# Connectors.net
KiCad netlist of a schematic drawn in Altium Designer
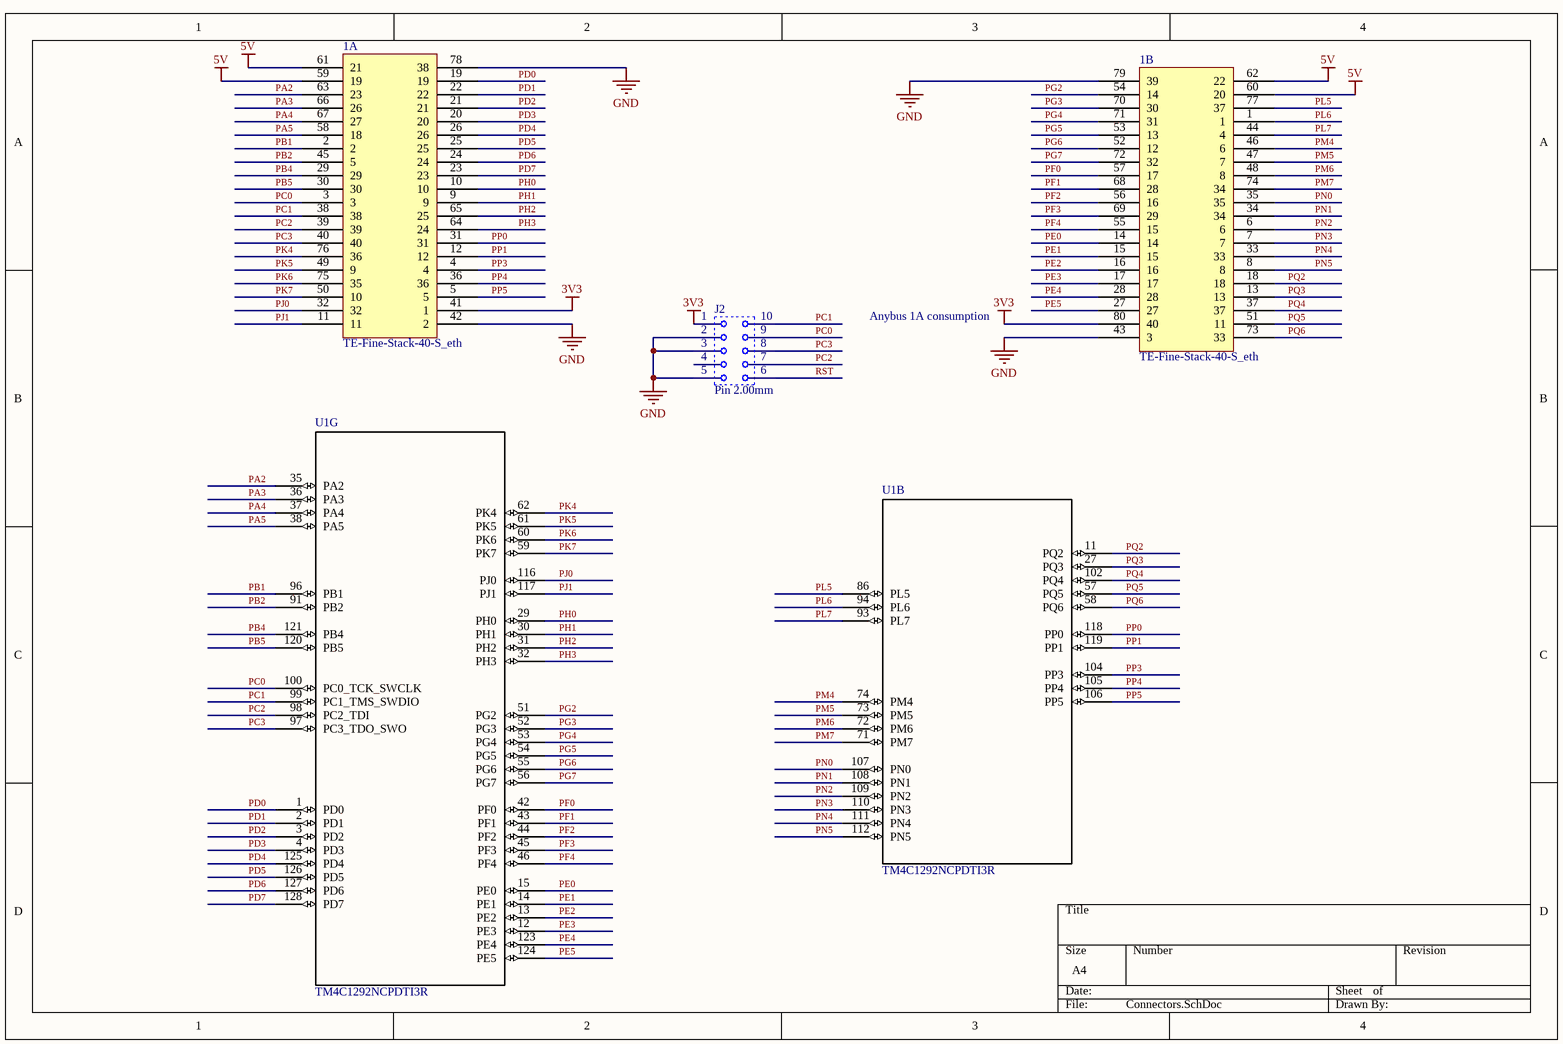
[diagram p0: Connectors.SchDoc]

(export (version "E")
  (design (tool "Eeschema 10.0.6"))
  (components
    (comp (ref "1")
      (value "TE-Fine-Stack-40-S_eth")
      (footprint "TE-FINE-STACK-40-S-Eth")
      (libsource (lib "Connectors") (part "TE-Fine-Stack-40-S_eth"))
    )
    (comp (ref "J2")
      (value "Pin 2.00mm")
      (footprint "GOLDPIN 1.27MM SOCKET 2X5 SMD")
      (libsource (lib "Connectors") (part "Goldpin 1.27 socket 2x5"))
    )
    (comp (ref "U1")
      (value "TM4C1292NCPDTI3R")
      (footprint "PDT0128A_N")
      (description "Imported")
      (fields
        (field (name "ALTERNATE PARTNUMBER") "TM4C1292NCPDTI3")
        (field (name "MANUFACTURER") "Texas Instruments")
      )
      (libsource (lib "TM4C129ENCPDT") (part "TM4C1292NCPDTI3R"))
    )
  )
  (nets
    (net (code "1") (name "/PA2") (class "Default")
      (node (ref "1") (pin "63") (pinfunction "23_63") (pintype "passive"))
      (node (ref "U1") (pin "35") (pinfunction "PA2_35") (pintype "bidirectional"))
    )
    (net (code "2") (name "/PA3") (class "Default")
      (node (ref "1") (pin "66") (pinfunction "26_66") (pintype "passive"))
      (node (ref "U1") (pin "36") (pinfunction "PA3_36") (pintype "bidirectional"))
    )
    (net (code "3") (name "/PA4") (class "Default")
      (node (ref "1") (pin "67") (pinfunction "27_67") (pintype "passive"))
      (node (ref "U1") (pin "37") (pinfunction "PA4_37") (pintype "bidirectional"))
    )
    (net (code "4") (name "/PA5") (class "Default")
      (node (ref "1") (pin "58") (pinfunction "18_58") (pintype "passive"))
      (node (ref "U1") (pin "38") (pinfunction "PA5_38") (pintype "bidirectional"))
    )
    (net (code "5") (name "/PB1") (class "Default")
      (node (ref "1") (pin "2") (pinfunction "2_2") (pintype "passive"))
      (node (ref "U1") (pin "96") (pinfunction "PB1_96") (pintype "bidirectional"))
    )
    (net (code "6") (name "/PB2") (class "Default")
      (node (ref "1") (pin "45") (pinfunction "5_45") (pintype "passive"))
      (node (ref "U1") (pin "91") (pinfunction "PB2_91") (pintype "bidirectional"))
    )
    (net (code "7") (name "/PB4") (class "Default")
      (node (ref "1") (pin "29") (pinfunction "29_29") (pintype "passive"))
      (node (ref "U1") (pin "121") (pinfunction "PB4_121") (pintype "bidirectional"))
    )
    (net (code "8") (name "/PB5") (class "Default")
      (node (ref "1") (pin "30") (pinfunction "30_30") (pintype "passive"))
      (node (ref "U1") (pin "120") (pinfunction "PB5_120") (pintype "bidirectional"))
    )
    (net (code "9") (name "/PC0") (class "Default")
      (node (ref "1") (pin "3") (pinfunction "3_3") (pintype "passive"))
      (node (ref "J2") (pin "9") (pintype "passive"))
      (node (ref "U1") (pin "100") (pinfunction "PC0_TCK_SWCLK_100") (pintype "bidirectional"))
    )
    (net (code "10") (name "/PC1") (class "Default")
      (node (ref "1") (pin "38") (pinfunction "38_38") (pintype "passive"))
      (node (ref "J2") (pin "10") (pintype "passive"))
      (node (ref "U1") (pin "99") (pinfunction "PC1_TMS_SWDIO_99") (pintype "bidirectional"))
    )
    (net (code "11") (name "/PC2") (class "Default")
      (node (ref "1") (pin "39") (pinfunction "39_39") (pintype "passive"))
      (node (ref "J2") (pin "7") (pintype "passive"))
      (node (ref "U1") (pin "98") (pinfunction "PC2_TDI_98") (pintype "bidirectional"))
    )
    (net (code "12") (name "/PC3") (class "Default")
      (node (ref "1") (pin "40") (pinfunction "40_40") (pintype "passive"))
      (node (ref "J2") (pin "8") (pintype "passive"))
      (node (ref "U1") (pin "97") (pinfunction "PC3_TDO_SWO_97") (pintype "bidirectional"))
    )
    (net (code "13") (name "/PD0") (class "Default")
      (node (ref "1") (pin "19") (pinfunction "19_19") (pintype "passive"))
      (node (ref "U1") (pin "1") (pinfunction "PD0_1") (pintype "bidirectional"))
    )
    (net (code "14") (name "/PD1") (class "Default")
      (node (ref "1") (pin "22") (pinfunction "22_22") (pintype "passive"))
      (node (ref "U1") (pin "2") (pinfunction "PD1_2") (pintype "bidirectional"))
    )
    (net (code "15") (name "/PD2") (class "Default")
      (node (ref "1") (pin "21") (pinfunction "21_21") (pintype "passive"))
      (node (ref "U1") (pin "3") (pinfunction "PD2_3") (pintype "bidirectional"))
    )
    (net (code "16") (name "/PD3") (class "Default")
      (node (ref "1") (pin "20") (pinfunction "20_20") (pintype "passive"))
      (node (ref "U1") (pin "4") (pinfunction "PD3_4") (pintype "bidirectional"))
    )
    (net (code "17") (name "/PD4") (class "Default")
      (node (ref "1") (pin "26") (pinfunction "26_26") (pintype "passive"))
      (node (ref "U1") (pin "125") (pinfunction "PD4_125") (pintype "bidirectional"))
    )
    (net (code "18") (name "/PD5") (class "Default")
      (node (ref "1") (pin "25") (pinfunction "25_25") (pintype "passive"))
      (node (ref "U1") (pin "126") (pinfunction "PD5_126") (pintype "bidirectional"))
    )
    (net (code "19") (name "/PD6") (class "Default")
      (node (ref "1") (pin "24") (pinfunction "24_24") (pintype "passive"))
      (node (ref "U1") (pin "127") (pinfunction "PD6_127") (pintype "bidirectional"))
    )
    (net (code "20") (name "/PD7") (class "Default")
      (node (ref "1") (pin "23") (pinfunction "23_23") (pintype "passive"))
      (node (ref "U1") (pin "128") (pinfunction "PD7_128") (pintype "bidirectional"))
    )
    (net (code "21") (name "/PE0") (class "Default")
      (node (ref "1") (pin "14") (pinfunction "14_14") (pintype "passive"))
      (node (ref "U1") (pin "15") (pinfunction "PE0_15") (pintype "bidirectional"))
    )
    (net (code "22") (name "/PE1") (class "Default")
      (node (ref "1") (pin "15") (pinfunction "15_15") (pintype "passive"))
      (node (ref "U1") (pin "14") (pinfunction "PE1_14") (pintype "bidirectional"))
    )
    (net (code "23") (name "/PE2") (class "Default")
      (node (ref "1") (pin "16") (pinfunction "16_16") (pintype "passive"))
      (node (ref "U1") (pin "13") (pinfunction "PE2_13") (pintype "bidirectional"))
    )
    (net (code "24") (name "/PE3") (class "Default")
      (node (ref "1") (pin "17") (pinfunction "17_17") (pintype "passive"))
      (node (ref "U1") (pin "12") (pinfunction "PE3_12") (pintype "bidirectional"))
    )
    (net (code "25") (name "/PE4") (class "Default")
      (node (ref "1") (pin "28") (pinfunction "28_28") (pintype "passive"))
      (node (ref "U1") (pin "123") (pinfunction "PE4_123") (pintype "bidirectional"))
    )
    (net (code "26") (name "/PE5") (class "Default")
      (node (ref "1") (pin "27") (pinfunction "27_27") (pintype "passive"))
      (node (ref "U1") (pin "124") (pinfunction "PE5_124") (pintype "bidirectional"))
    )
    (net (code "27") (name "/PF0") (class "Default")
      (node (ref "1") (pin "57") (pinfunction "17_57") (pintype "passive"))
      (node (ref "U1") (pin "42") (pinfunction "PF0_42") (pintype "bidirectional"))
    )
    (net (code "28") (name "/PF1") (class "Default")
      (node (ref "1") (pin "68") (pinfunction "28_68") (pintype "passive"))
      (node (ref "U1") (pin "43") (pinfunction "PF1_43") (pintype "bidirectional"))
    )
    (net (code "29") (name "/PF2") (class "Default")
      (node (ref "1") (pin "56") (pinfunction "16_56") (pintype "passive"))
      (node (ref "U1") (pin "44") (pinfunction "PF2_44") (pintype "bidirectional"))
    )
    (net (code "30") (name "/PF3") (class "Default")
      (node (ref "1") (pin "69") (pinfunction "29_69") (pintype "passive"))
      (node (ref "U1") (pin "45") (pinfunction "PF3_45") (pintype "bidirectional"))
    )
    (net (code "31") (name "/PF4") (class "Default")
      (node (ref "1") (pin "55") (pinfunction "15_55") (pintype "passive"))
      (node (ref "U1") (pin "46") (pinfunction "PF4_46") (pintype "bidirectional"))
    )
    (net (code "32") (name "/PG2") (class "Default")
      (node (ref "1") (pin "54") (pinfunction "14_54") (pintype "passive"))
      (node (ref "U1") (pin "51") (pinfunction "PG2_51") (pintype "bidirectional"))
    )
    (net (code "33") (name "/PG3") (class "Default")
      (node (ref "1") (pin "70") (pinfunction "30_70") (pintype "passive"))
      (node (ref "U1") (pin "52") (pinfunction "PG3_52") (pintype "bidirectional"))
    )
    (net (code "34") (name "/PG4") (class "Default")
      (node (ref "1") (pin "71") (pinfunction "31_71") (pintype "passive"))
      (node (ref "U1") (pin "53") (pinfunction "PG4_53") (pintype "bidirectional"))
    )
    (net (code "35") (name "/PG5") (class "Default")
      (node (ref "1") (pin "53") (pinfunction "13_53") (pintype "passive"))
      (node (ref "U1") (pin "54") (pinfunction "PG5_54") (pintype "bidirectional"))
    )
    (net (code "36") (name "/PG6") (class "Default")
      (node (ref "1") (pin "52") (pinfunction "12_52") (pintype "passive"))
      (node (ref "U1") (pin "55") (pinfunction "PG6_55") (pintype "bidirectional"))
    )
    (net (code "37") (name "/PG7") (class "Default")
      (node (ref "1") (pin "72") (pinfunction "32_72") (pintype "passive"))
      (node (ref "U1") (pin "56") (pinfunction "PG7_56") (pintype "bidirectional"))
    )
    (net (code "38") (name "/PH0") (class "Default")
      (node (ref "1") (pin "10") (pinfunction "10_10") (pintype "passive"))
      (node (ref "U1") (pin "29") (pinfunction "PH0_29") (pintype "bidirectional"))
    )
    (net (code "39") (name "/PH1") (class "Default")
      (node (ref "1") (pin "9") (pinfunction "9_9") (pintype "passive"))
      (node (ref "U1") (pin "30") (pinfunction "PH1_30") (pintype "bidirectional"))
    )
    (net (code "40") (name "/PH2") (class "Default")
      (node (ref "1") (pin "65") (pinfunction "25_65") (pintype "passive"))
      (node (ref "U1") (pin "31") (pinfunction "PH2_31") (pintype "bidirectional"))
    )
    (net (code "41") (name "/PH3") (class "Default")
      (node (ref "1") (pin "64") (pinfunction "24_64") (pintype "passive"))
      (node (ref "U1") (pin "32") (pinfunction "PH3_32") (pintype "bidirectional"))
    )
    (net (code "42") (name "/PJ0") (class "Default")
      (node (ref "1") (pin "32") (pinfunction "32_32") (pintype "passive"))
      (node (ref "U1") (pin "116") (pinfunction "PJ0_116") (pintype "bidirectional"))
    )
    (net (code "43") (name "/PJ1") (class "Default")
      (node (ref "1") (pin "11") (pinfunction "11_11") (pintype "passive"))
      (node (ref "U1") (pin "117") (pinfunction "PJ1_117") (pintype "bidirectional"))
    )
    (net (code "44") (name "/PK4") (class "Default")
      (node (ref "1") (pin "76") (pinfunction "36_76") (pintype "passive"))
      (node (ref "U1") (pin "62") (pinfunction "PK4_62") (pintype "bidirectional"))
    )
    (net (code "45") (name "/PK5") (class "Default")
      (node (ref "1") (pin "49") (pinfunction "9_49") (pintype "passive"))
      (node (ref "U1") (pin "61") (pinfunction "PK5_61") (pintype "bidirectional"))
    )
    (net (code "46") (name "/PK6") (class "Default")
      (node (ref "1") (pin "75") (pinfunction "35_75") (pintype "passive"))
      (node (ref "U1") (pin "60") (pinfunction "PK6_60") (pintype "bidirectional"))
    )
    (net (code "47") (name "/PK7") (class "Default")
      (node (ref "1") (pin "50") (pinfunction "10_50") (pintype "passive"))
      (node (ref "U1") (pin "59") (pinfunction "PK7_59") (pintype "bidirectional"))
    )
    (net (code "48") (name "/PL5") (class "Default")
      (node (ref "1") (pin "77") (pinfunction "37_77") (pintype "passive"))
      (node (ref "U1") (pin "86") (pinfunction "PL5_86") (pintype "bidirectional"))
    )
    (net (code "49") (name "/PL6") (class "Default")
      (node (ref "1") (pin "1") (pinfunction "1_1") (pintype "passive"))
      (node (ref "U1") (pin "94") (pinfunction "PL6_94") (pintype "bidirectional"))
    )
    (net (code "50") (name "/PL7") (class "Default")
      (node (ref "1") (pin "44") (pinfunction "4_44") (pintype "passive"))
      (node (ref "U1") (pin "93") (pinfunction "PL7_93") (pintype "bidirectional"))
    )
    (net (code "51") (name "/PM4") (class "Default")
      (node (ref "1") (pin "46") (pinfunction "6_46") (pintype "passive"))
      (node (ref "U1") (pin "74") (pinfunction "PM4_74") (pintype "bidirectional"))
    )
    (net (code "52") (name "/PM5") (class "Default")
      (node (ref "1") (pin "47") (pinfunction "7_47") (pintype "passive"))
      (node (ref "U1") (pin "73") (pinfunction "PM5_73") (pintype "bidirectional"))
    )
    (net (code "53") (name "/PM6") (class "Default")
      (node (ref "1") (pin "48") (pinfunction "8_48") (pintype "passive"))
      (node (ref "U1") (pin "72") (pinfunction "PM6_72") (pintype "bidirectional"))
    )
    (net (code "54") (name "/PM7") (class "Default")
      (node (ref "1") (pin "74") (pinfunction "34_74") (pintype "passive"))
      (node (ref "U1") (pin "71") (pinfunction "PM7_71") (pintype "bidirectional"))
    )
    (net (code "55") (name "/PN0") (class "Default")
      (node (ref "1") (pin "35") (pinfunction "35_35") (pintype "passive"))
      (node (ref "U1") (pin "107") (pinfunction "PN0_107") (pintype "bidirectional"))
    )
    (net (code "56") (name "/PN1") (class "Default")
      (node (ref "1") (pin "34") (pinfunction "34_34") (pintype "passive"))
      (node (ref "U1") (pin "108") (pinfunction "PN1_108") (pintype "bidirectional"))
    )
    (net (code "57") (name "/PN2") (class "Default")
      (node (ref "1") (pin "6") (pinfunction "6_6") (pintype "passive"))
      (node (ref "U1") (pin "109") (pinfunction "PN2_109") (pintype "bidirectional"))
    )
    (net (code "58") (name "/PN3") (class "Default")
      (node (ref "1") (pin "7") (pinfunction "7_7") (pintype "passive"))
      (node (ref "U1") (pin "110") (pinfunction "PN3_110") (pintype "bidirectional"))
    )
    (net (code "59") (name "/PN4") (class "Default")
      (node (ref "1") (pin "33") (pinfunction "33_33") (pintype "passive"))
      (node (ref "U1") (pin "111") (pinfunction "PN4_111") (pintype "bidirectional"))
    )
    (net (code "60") (name "/PN5") (class "Default")
      (node (ref "1") (pin "8") (pinfunction "8_8") (pintype "passive"))
      (node (ref "U1") (pin "112") (pinfunction "PN5_112") (pintype "bidirectional"))
    )
    (net (code "61") (name "/PP0") (class "Default")
      (node (ref "1") (pin "31") (pinfunction "31_31") (pintype "passive"))
      (node (ref "U1") (pin "118") (pinfunction "PP0_118") (pintype "bidirectional"))
    )
    (net (code "62") (name "/PP1") (class "Default")
      (node (ref "1") (pin "12") (pinfunction "12_12") (pintype "passive"))
      (node (ref "U1") (pin "119") (pinfunction "PP1_119") (pintype "bidirectional"))
    )
    (net (code "63") (name "/PP3") (class "Default")
      (node (ref "1") (pin "4") (pinfunction "4_4") (pintype "passive"))
      (node (ref "U1") (pin "104") (pinfunction "PP3_104") (pintype "bidirectional"))
    )
    (net (code "64") (name "/PP4") (class "Default")
      (node (ref "1") (pin "36") (pinfunction "36_36") (pintype "passive"))
      (node (ref "U1") (pin "105") (pinfunction "PP4_105") (pintype "bidirectional"))
    )
    (net (code "65") (name "/PP5") (class "Default")
      (node (ref "1") (pin "5") (pinfunction "5_5") (pintype "passive"))
      (node (ref "U1") (pin "106") (pinfunction "PP5_106") (pintype "bidirectional"))
    )
    (net (code "66") (name "/PQ2") (class "Default")
      (node (ref "1") (pin "18") (pinfunction "18_18") (pintype "passive"))
      (node (ref "U1") (pin "11") (pinfunction "PQ2_11") (pintype "bidirectional"))
    )
    (net (code "67") (name "/PQ3") (class "Default")
      (node (ref "1") (pin "13") (pinfunction "13_13") (pintype "passive"))
      (node (ref "U1") (pin "27") (pinfunction "PQ3_27") (pintype "bidirectional"))
    )
    (net (code "68") (name "/PQ4") (class "Default")
      (node (ref "1") (pin "37") (pinfunction "37_37") (pintype "passive"))
      (node (ref "U1") (pin "102") (pinfunction "PQ4_102") (pintype "bidirectional"))
    )
    (net (code "69") (name "/PQ5") (class "Default")
      (node (ref "1") (pin "51") (pinfunction "11_51") (pintype "passive"))
      (node (ref "U1") (pin "57") (pinfunction "PQ5_57") (pintype "bidirectional"))
    )
    (net (code "70") (name "/PQ6") (class "Default")
      (node (ref "1") (pin "73") (pinfunction "33_73") (pintype "passive"))
      (node (ref "U1") (pin "58") (pinfunction "PQ6_58") (pintype "bidirectional"))
    )
    (net (code "71") (name "/RST") (class "Default") (node (ref "J2") (pin "6") (pintype "passive")))
    (net (code "72") (name "3V3") (class "Default")
      (node (ref "1") (pin "41") (pinfunction "1_41") (pintype "passive"))
      (node (ref "1") (pin "80") (pinfunction "40_80") (pintype "passive"))
      (node (ref "J2") (pin "1") (pintype "passive"))
    )
    (net (code "73") (name "5V") (class "Default")
      (node (ref "1") (pin "59") (pinfunction "19_59") (pintype "passive"))
      (node (ref "1") (pin "60") (pinfunction "20_60") (pintype "passive"))
      (node (ref "1") (pin "61") (pinfunction "21_61") (pintype "passive"))
      (node (ref "1") (pin "62") (pinfunction "22_62") (pintype "passive"))
    )
    (net (code "74") (name "GND") (class "Default")
      (node (ref "1") (pin "42") (pinfunction "2_42") (pintype "passive"))
      (node (ref "1") (pin "43") (pinfunction "3_43") (pintype "passive"))
      (node (ref "1") (pin "78") (pinfunction "38_78") (pintype "passive"))
      (node (ref "1") (pin "79") (pinfunction "39_79") (pintype "passive"))
      (node (ref "J2") (pin "2") (pintype "passive"))
      (node (ref "J2") (pin "3") (pintype "passive"))
      (node (ref "J2") (pin "5") (pintype "passive"))
    )
    (net (code "75") (name "unconnected-(J2-Pad4)") (class "Default")
      (node (ref "J2") (pin "4") (pintype "passive"))
    )
  )
)
